# dual-dac-w-32-ch-sh-SH-BOARD.net
KiCad netlist of a schematic drawn in EAGLE
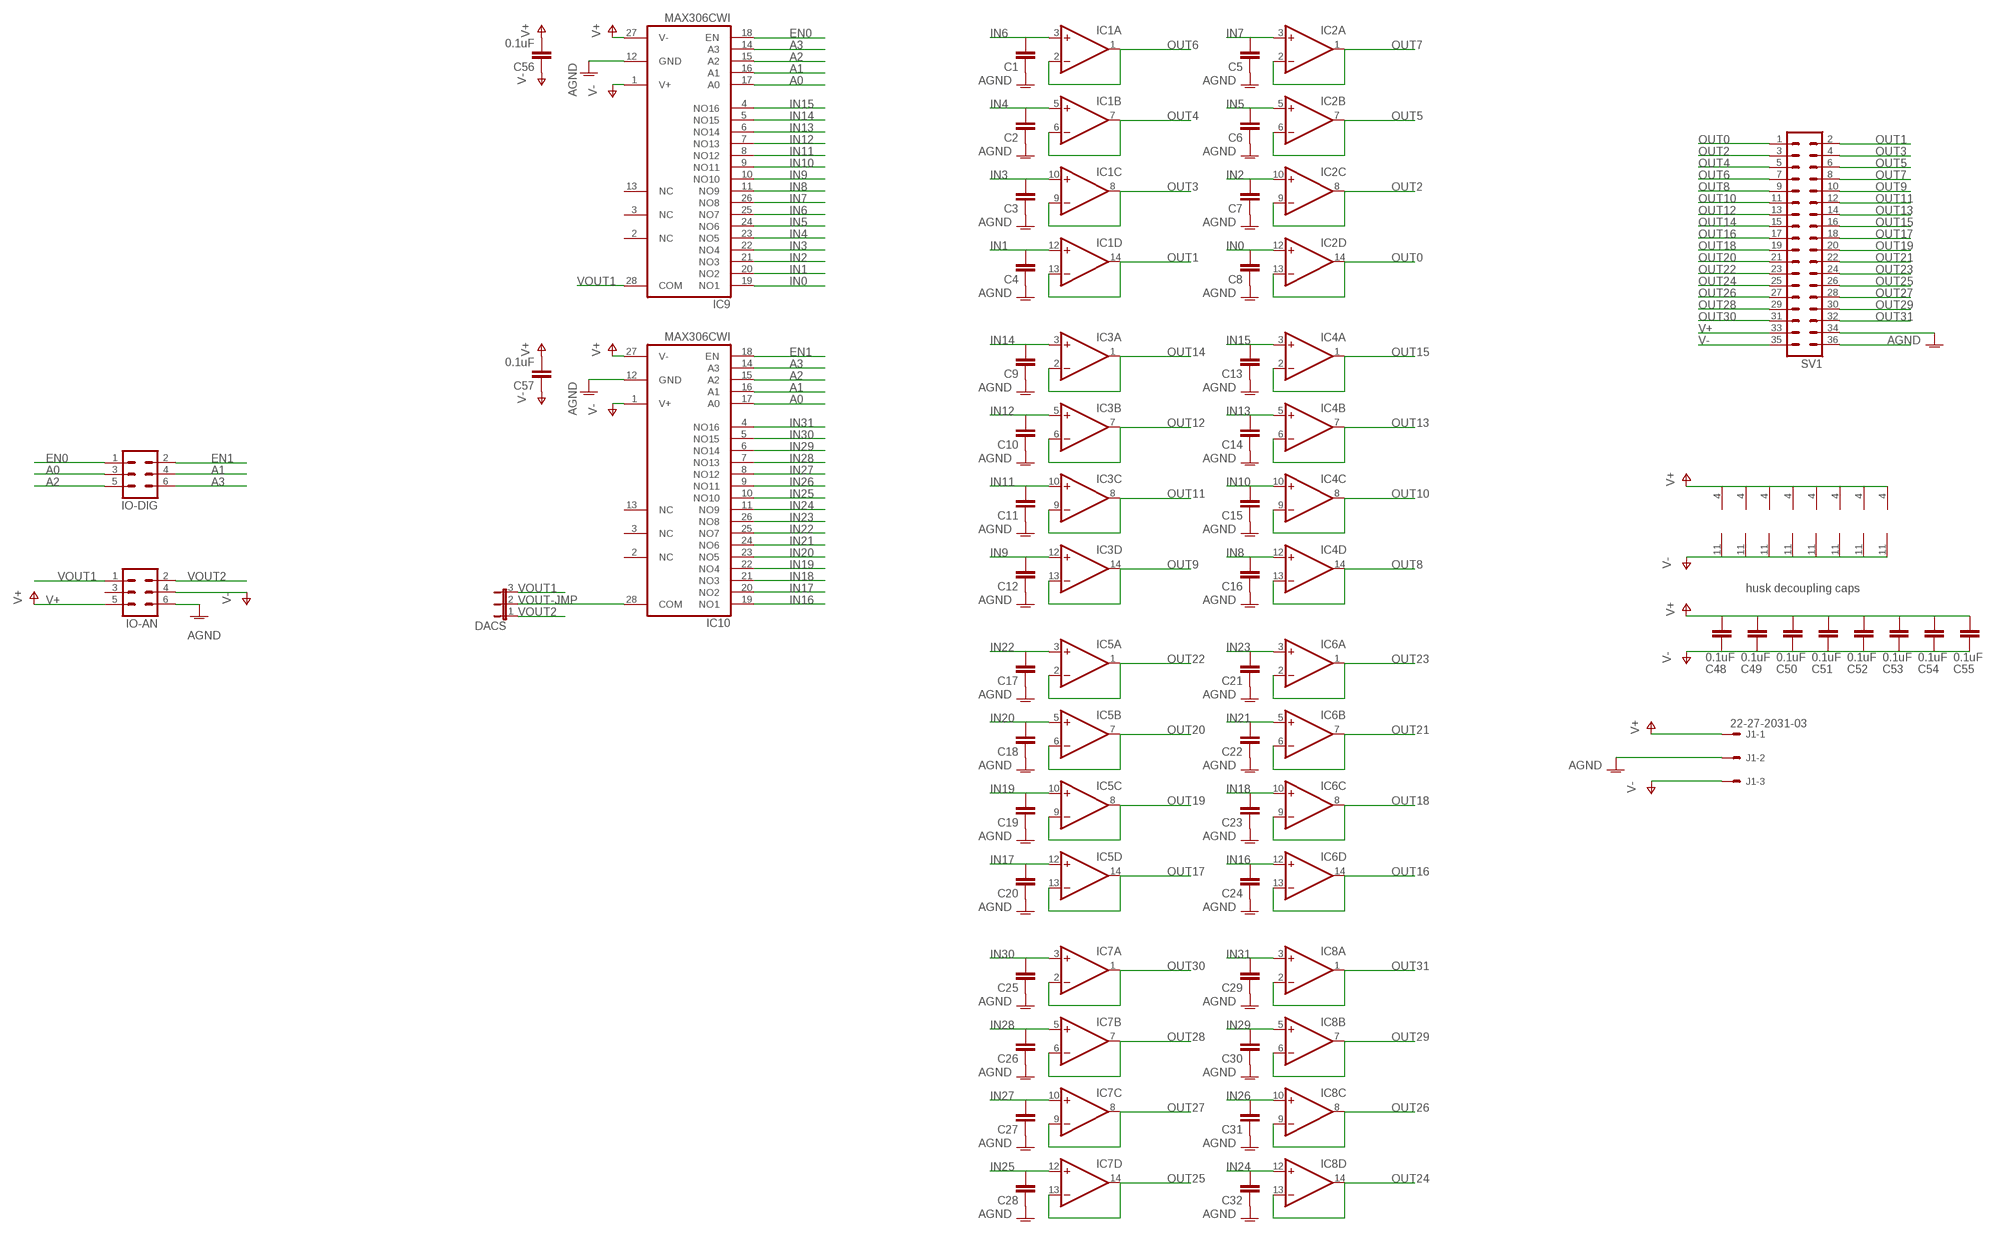
[diagram p0: schematic, sheet 1]

(export (version "E")
  (design (tool "Eeschema 10.0.6"))
  (components
    (comp (ref "C1")
      (value "C-EUC1206")
      (footprint "eagle-import:C1206")
      (libsource (lib "eagle-import") (part "C-EUC1206"))
    )
    (comp (ref "C2")
      (value "C-EUC1206")
      (footprint "eagle-import:C1206")
      (libsource (lib "eagle-import") (part "C-EUC1206"))
    )
    (comp (ref "C3")
      (value "C-EUC1206")
      (footprint "eagle-import:C1206")
      (libsource (lib "eagle-import") (part "C-EUC1206"))
    )
    (comp (ref "C4")
      (value "C-EUC1206")
      (footprint "eagle-import:C1206")
      (libsource (lib "eagle-import") (part "C-EUC1206"))
    )
    (comp (ref "C5")
      (value "C-EUC1206")
      (footprint "eagle-import:C1206")
      (libsource (lib "eagle-import") (part "C-EUC1206"))
    )
    (comp (ref "C6")
      (value "C-EUC1206")
      (footprint "eagle-import:C1206")
      (libsource (lib "eagle-import") (part "C-EUC1206"))
    )
    (comp (ref "C7")
      (value "C-EUC1206")
      (footprint "eagle-import:C1206")
      (libsource (lib "eagle-import") (part "C-EUC1206"))
    )
    (comp (ref "C8")
      (value "C-EUC1206")
      (footprint "eagle-import:C1206")
      (libsource (lib "eagle-import") (part "C-EUC1206"))
    )
    (comp (ref "C9")
      (value "C-EUC1206")
      (footprint "eagle-import:C1206")
      (libsource (lib "eagle-import") (part "C-EUC1206"))
    )
    (comp (ref "C10")
      (value "C-EUC1206")
      (footprint "eagle-import:C1206")
      (libsource (lib "eagle-import") (part "C-EUC1206"))
    )
    (comp (ref "C11")
      (value "C-EUC1206")
      (footprint "eagle-import:C1206")
      (libsource (lib "eagle-import") (part "C-EUC1206"))
    )
    (comp (ref "C12")
      (value "C-EUC1206")
      (footprint "eagle-import:C1206")
      (libsource (lib "eagle-import") (part "C-EUC1206"))
    )
    (comp (ref "C13")
      (value "C-EUC1206")
      (footprint "eagle-import:C1206")
      (libsource (lib "eagle-import") (part "C-EUC1206"))
    )
    (comp (ref "C14")
      (value "C-EUC1206")
      (footprint "eagle-import:C1206")
      (libsource (lib "eagle-import") (part "C-EUC1206"))
    )
    (comp (ref "C15")
      (value "C-EUC1206")
      (footprint "eagle-import:C1206")
      (libsource (lib "eagle-import") (part "C-EUC1206"))
    )
    (comp (ref "C16")
      (value "C-EUC1206")
      (footprint "eagle-import:C1206")
      (libsource (lib "eagle-import") (part "C-EUC1206"))
    )
    (comp (ref "C17")
      (value "C-EUC1206")
      (footprint "eagle-import:C1206")
      (libsource (lib "eagle-import") (part "C-EUC1206"))
    )
    (comp (ref "C18")
      (value "C-EUC1206")
      (footprint "eagle-import:C1206")
      (libsource (lib "eagle-import") (part "C-EUC1206"))
    )
    (comp (ref "C19")
      (value "C-EUC1206")
      (footprint "eagle-import:C1206")
      (libsource (lib "eagle-import") (part "C-EUC1206"))
    )
    (comp (ref "C20")
      (value "C-EUC1206")
      (footprint "eagle-import:C1206")
      (libsource (lib "eagle-import") (part "C-EUC1206"))
    )
    (comp (ref "C21")
      (value "C-EUC1206")
      (footprint "eagle-import:C1206")
      (libsource (lib "eagle-import") (part "C-EUC1206"))
    )
    (comp (ref "C22")
      (value "C-EUC1206")
      (footprint "eagle-import:C1206")
      (libsource (lib "eagle-import") (part "C-EUC1206"))
    )
    (comp (ref "C23")
      (value "C-EUC1206")
      (footprint "eagle-import:C1206")
      (libsource (lib "eagle-import") (part "C-EUC1206"))
    )
    (comp (ref "C24")
      (value "C-EUC1206")
      (footprint "eagle-import:C1206")
      (libsource (lib "eagle-import") (part "C-EUC1206"))
    )
    (comp (ref "C25")
      (value "C-EUC1206")
      (footprint "eagle-import:C1206")
      (libsource (lib "eagle-import") (part "C-EUC1206"))
    )
    (comp (ref "C26")
      (value "C-EUC1206")
      (footprint "eagle-import:C1206")
      (libsource (lib "eagle-import") (part "C-EUC1206"))
    )
    (comp (ref "C27")
      (value "C-EUC1206")
      (footprint "eagle-import:C1206")
      (libsource (lib "eagle-import") (part "C-EUC1206"))
    )
    (comp (ref "C28")
      (value "C-EUC1206")
      (footprint "eagle-import:C1206")
      (libsource (lib "eagle-import") (part "C-EUC1206"))
    )
    (comp (ref "C29")
      (value "C-EUC1206")
      (footprint "eagle-import:C1206")
      (libsource (lib "eagle-import") (part "C-EUC1206"))
    )
    (comp (ref "C30")
      (value "C-EUC1206")
      (footprint "eagle-import:C1206")
      (libsource (lib "eagle-import") (part "C-EUC1206"))
    )
    (comp (ref "C31")
      (value "C-EUC1206")
      (footprint "eagle-import:C1206")
      (libsource (lib "eagle-import") (part "C-EUC1206"))
    )
    (comp (ref "C32")
      (value "C-EUC1206")
      (footprint "eagle-import:C1206")
      (libsource (lib "eagle-import") (part "C-EUC1206"))
    )
    (comp (ref "C48")
      (value "0.1uF")
      (footprint "eagle-import:C0603")
      (libsource (lib "eagle-import") (part "C-EUC0603"))
    )
    (comp (ref "C49")
      (value "0.1uF")
      (footprint "eagle-import:C0603")
      (libsource (lib "eagle-import") (part "C-EUC0603"))
    )
    (comp (ref "C50")
      (value "0.1uF")
      (footprint "eagle-import:C0603")
      (libsource (lib "eagle-import") (part "C-EUC0603"))
    )
    (comp (ref "C51")
      (value "0.1uF")
      (footprint "eagle-import:C0603")
      (libsource (lib "eagle-import") (part "C-EUC0603"))
    )
    (comp (ref "C52")
      (value "0.1uF")
      (footprint "eagle-import:C0603")
      (libsource (lib "eagle-import") (part "C-EUC0603"))
    )
    (comp (ref "C53")
      (value "0.1uF")
      (footprint "eagle-import:C0603")
      (libsource (lib "eagle-import") (part "C-EUC0603"))
    )
    (comp (ref "C54")
      (value "0.1uF")
      (footprint "eagle-import:C0603")
      (libsource (lib "eagle-import") (part "C-EUC0603"))
    )
    (comp (ref "C55")
      (value "0.1uF")
      (footprint "eagle-import:C0603")
      (libsource (lib "eagle-import") (part "C-EUC0603"))
    )
    (comp (ref "C56")
      (value "0.1uF")
      (footprint "eagle-import:C0603")
      (libsource (lib "eagle-import") (part "C-EUC0603"))
    )
    (comp (ref "C57")
      (value "0.1uF")
      (footprint "eagle-import:C0603")
      (libsource (lib "eagle-import") (part "C-EUC0603"))
    )
    (comp (ref "DACS")
      (value "JP2E")
      (footprint "eagle-import:JP2")
      (libsource (lib "eagle-import") (part "JP2E"))
    )
    (comp (ref "IC1")
      (value "TL074D")
      (footprint "eagle-import:SO14")
      (libsource (lib "eagle-import") (part "TL074D"))
    )
    (comp (ref "IC2")
      (value "TL074D")
      (footprint "eagle-import:SO14")
      (libsource (lib "eagle-import") (part "TL074D"))
    )
    (comp (ref "IC3")
      (value "TL074D")
      (footprint "eagle-import:SO14")
      (libsource (lib "eagle-import") (part "TL074D"))
    )
    (comp (ref "IC4")
      (value "TL074D")
      (footprint "eagle-import:SO14")
      (libsource (lib "eagle-import") (part "TL074D"))
    )
    (comp (ref "IC5")
      (value "TL074D")
      (footprint "eagle-import:SO14")
      (libsource (lib "eagle-import") (part "TL074D"))
    )
    (comp (ref "IC6")
      (value "TL074D")
      (footprint "eagle-import:SO14")
      (libsource (lib "eagle-import") (part "TL074D"))
    )
    (comp (ref "IC7")
      (value "TL074D")
      (footprint "eagle-import:SO14")
      (libsource (lib "eagle-import") (part "TL074D"))
    )
    (comp (ref "IC8")
      (value "TL074D")
      (footprint "eagle-import:SO14")
      (libsource (lib "eagle-import") (part "TL074D"))
    )
    (comp (ref "IC9")
      (value "MAX306CWI")
      (footprint "eagle-import:SO28L")
      (fields (field (name "MF") "MAXIM"))
      (libsource (lib "eagle-import") (part "MAX306CWI"))
    )
    (comp (ref "IC10")
      (value "MAX306CWI")
      (footprint "eagle-import:SO28L")
      (fields (field (name "MF") "MAXIM"))
      (libsource (lib "eagle-import") (part "MAX306CWI"))
    )
    (comp (ref "IO-AN")
      (value "MA03-2")
      (footprint "eagle-import:MA03-2")
      (libsource (lib "eagle-import") (part "MA03-2"))
    )
    (comp (ref "IO-DIG")
      (value "MA03-2")
      (footprint "eagle-import:MA03-2")
      (libsource (lib "eagle-import") (part "MA03-2"))
    )
    (comp (ref "J1")
      (value "22-27-2031-03")
      (footprint "eagle-import:6410-03")
      (libsource (lib "eagle-import") (part "22-?-0327-2031"))
    )
    (comp (ref "SV1")
      (value "MA18-2")
      (footprint "eagle-import:MA18-2")
      (libsource (lib "eagle-import") (part "MA18-2"))
    )
  )
  (nets
    (net (code "1") (name "/A0") (class "Default")
      (node (ref "IC10") (pin "17") (pinfunction "A0_17") (pintype "input"))
      (node (ref "IC9") (pin "17") (pinfunction "A0_17") (pintype "input"))
      (node (ref "IO-DIG") (pin "3") (pinfunction "3_3") (pintype "passive"))
    )
    (net (code "2") (name "/A1") (class "Default")
      (node (ref "IC10") (pin "16") (pinfunction "A1_16") (pintype "input"))
      (node (ref "IC9") (pin "16") (pinfunction "A1_16") (pintype "input"))
      (node (ref "IO-DIG") (pin "4") (pinfunction "4_4") (pintype "passive"))
    )
    (net (code "3") (name "/A2") (class "Default")
      (node (ref "IC10") (pin "15") (pinfunction "A2_15") (pintype "input"))
      (node (ref "IC9") (pin "15") (pinfunction "A2_15") (pintype "input"))
      (node (ref "IO-DIG") (pin "5") (pinfunction "5_5") (pintype "passive"))
    )
    (net (code "4") (name "/A3") (class "Default")
      (node (ref "IC10") (pin "14") (pinfunction "A3_14") (pintype "input"))
      (node (ref "IC9") (pin "14") (pinfunction "A3_14") (pintype "input"))
      (node (ref "IO-DIG") (pin "6") (pinfunction "6_6") (pintype "passive"))
    )
    (net (code "5") (name "/EN0") (class "Default")
      (node (ref "IC9") (pin "18") (pinfunction "EN_18") (pintype "input"))
      (node (ref "IO-DIG") (pin "1") (pinfunction "1_1") (pintype "passive"))
    )
    (net (code "6") (name "/EN1") (class "Default")
      (node (ref "IC10") (pin "18") (pinfunction "EN_18") (pintype "input"))
      (node (ref "IO-DIG") (pin "2") (pinfunction "2_2") (pintype "passive"))
    )
    (net (code "7") (name "/IN0") (class "Default")
      (node (ref "C8") (pin "2") (pinfunction "2_2") (pintype "passive"))
      (node (ref "IC2") (pin "12") (pinfunction "+IN_12") (pintype "input"))
      (node (ref "IC9") (pin "19") (pinfunction "NO1_19") (pintype "passive"))
    )
    (net (code "8") (name "/IN1") (class "Default")
      (node (ref "C4") (pin "2") (pinfunction "2_2") (pintype "passive"))
      (node (ref "IC1") (pin "12") (pinfunction "+IN_12") (pintype "input"))
      (node (ref "IC9") (pin "20") (pinfunction "NO2_20") (pintype "passive"))
    )
    (net (code "9") (name "/IN2") (class "Default")
      (node (ref "C7") (pin "2") (pinfunction "2_2") (pintype "passive"))
      (node (ref "IC2") (pin "10") (pinfunction "+IN_10") (pintype "input"))
      (node (ref "IC9") (pin "21") (pinfunction "NO3_21") (pintype "passive"))
    )
    (net (code "10") (name "/IN3") (class "Default")
      (node (ref "C3") (pin "2") (pinfunction "2_2") (pintype "passive"))
      (node (ref "IC1") (pin "10") (pinfunction "+IN_10") (pintype "input"))
      (node (ref "IC9") (pin "22") (pinfunction "NO4_22") (pintype "passive"))
    )
    (net (code "11") (name "/IN4") (class "Default")
      (node (ref "C2") (pin "2") (pinfunction "2_2") (pintype "passive"))
      (node (ref "IC1") (pin "5") (pinfunction "+IN_5") (pintype "input"))
      (node (ref "IC9") (pin "23") (pinfunction "NO5_23") (pintype "passive"))
    )
    (net (code "12") (name "/IN5") (class "Default")
      (node (ref "C6") (pin "2") (pinfunction "2_2") (pintype "passive"))
      (node (ref "IC2") (pin "5") (pinfunction "+IN_5") (pintype "input"))
      (node (ref "IC9") (pin "24") (pinfunction "NO6_24") (pintype "passive"))
    )
    (net (code "13") (name "/IN6") (class "Default")
      (node (ref "C1") (pin "2") (pinfunction "2_2") (pintype "passive"))
      (node (ref "IC1") (pin "3") (pinfunction "+IN_3") (pintype "input"))
      (node (ref "IC9") (pin "25") (pinfunction "NO7_25") (pintype "passive"))
    )
    (net (code "14") (name "/IN7") (class "Default")
      (node (ref "C5") (pin "2") (pinfunction "2_2") (pintype "passive"))
      (node (ref "IC2") (pin "3") (pinfunction "+IN_3") (pintype "input"))
      (node (ref "IC9") (pin "26") (pinfunction "NO8_26") (pintype "passive"))
    )
    (net (code "15") (name "/IN8") (class "Default")
      (node (ref "C16") (pin "2") (pinfunction "2_2") (pintype "passive"))
      (node (ref "IC4") (pin "12") (pinfunction "+IN_12") (pintype "input"))
      (node (ref "IC9") (pin "11") (pinfunction "NO9_11") (pintype "passive"))
    )
    (net (code "16") (name "/IN9") (class "Default")
      (node (ref "C12") (pin "2") (pinfunction "2_2") (pintype "passive"))
      (node (ref "IC3") (pin "12") (pinfunction "+IN_12") (pintype "input"))
      (node (ref "IC9") (pin "10") (pinfunction "NO10_10") (pintype "passive"))
    )
    (net (code "17") (name "/IN10") (class "Default")
      (node (ref "C15") (pin "2") (pinfunction "2_2") (pintype "passive"))
      (node (ref "IC4") (pin "10") (pinfunction "+IN_10") (pintype "input"))
      (node (ref "IC9") (pin "9") (pinfunction "NO11_9") (pintype "passive"))
    )
    (net (code "18") (name "/IN11") (class "Default")
      (node (ref "C11") (pin "2") (pinfunction "2_2") (pintype "passive"))
      (node (ref "IC3") (pin "10") (pinfunction "+IN_10") (pintype "input"))
      (node (ref "IC9") (pin "8") (pinfunction "NO12_8") (pintype "passive"))
    )
    (net (code "19") (name "/IN12") (class "Default")
      (node (ref "C10") (pin "2") (pinfunction "2_2") (pintype "passive"))
      (node (ref "IC3") (pin "5") (pinfunction "+IN_5") (pintype "input"))
      (node (ref "IC9") (pin "7") (pinfunction "NO13_7") (pintype "passive"))
    )
    (net (code "20") (name "/IN13") (class "Default")
      (node (ref "C14") (pin "2") (pinfunction "2_2") (pintype "passive"))
      (node (ref "IC4") (pin "5") (pinfunction "+IN_5") (pintype "input"))
      (node (ref "IC9") (pin "6") (pinfunction "NO14_6") (pintype "passive"))
    )
    (net (code "21") (name "/IN14") (class "Default")
      (node (ref "C9") (pin "2") (pinfunction "2_2") (pintype "passive"))
      (node (ref "IC3") (pin "3") (pinfunction "+IN_3") (pintype "input"))
      (node (ref "IC9") (pin "5") (pinfunction "NO15_5") (pintype "passive"))
    )
    (net (code "22") (name "/IN15") (class "Default")
      (node (ref "C13") (pin "2") (pinfunction "2_2") (pintype "passive"))
      (node (ref "IC4") (pin "3") (pinfunction "+IN_3") (pintype "input"))
      (node (ref "IC9") (pin "4") (pinfunction "NO16_4") (pintype "passive"))
    )
    (net (code "23") (name "/IN16") (class "Default")
      (node (ref "C24") (pin "2") (pinfunction "2_2") (pintype "passive"))
      (node (ref "IC10") (pin "19") (pinfunction "NO1_19") (pintype "passive"))
      (node (ref "IC6") (pin "12") (pinfunction "+IN_12") (pintype "input"))
    )
    (net (code "24") (name "/IN17") (class "Default")
      (node (ref "C20") (pin "2") (pinfunction "2_2") (pintype "passive"))
      (node (ref "IC10") (pin "20") (pinfunction "NO2_20") (pintype "passive"))
      (node (ref "IC5") (pin "12") (pinfunction "+IN_12") (pintype "input"))
    )
    (net (code "25") (name "/IN18") (class "Default")
      (node (ref "C23") (pin "2") (pinfunction "2_2") (pintype "passive"))
      (node (ref "IC10") (pin "21") (pinfunction "NO3_21") (pintype "passive"))
      (node (ref "IC6") (pin "10") (pinfunction "+IN_10") (pintype "input"))
    )
    (net (code "26") (name "/IN19") (class "Default")
      (node (ref "C19") (pin "2") (pinfunction "2_2") (pintype "passive"))
      (node (ref "IC10") (pin "22") (pinfunction "NO4_22") (pintype "passive"))
      (node (ref "IC5") (pin "10") (pinfunction "+IN_10") (pintype "input"))
    )
    (net (code "27") (name "/IN20") (class "Default")
      (node (ref "C18") (pin "2") (pinfunction "2_2") (pintype "passive"))
      (node (ref "IC10") (pin "23") (pinfunction "NO5_23") (pintype "passive"))
      (node (ref "IC5") (pin "5") (pinfunction "+IN_5") (pintype "input"))
    )
    (net (code "28") (name "/IN21") (class "Default")
      (node (ref "C22") (pin "2") (pinfunction "2_2") (pintype "passive"))
      (node (ref "IC10") (pin "24") (pinfunction "NO6_24") (pintype "passive"))
      (node (ref "IC6") (pin "5") (pinfunction "+IN_5") (pintype "input"))
    )
    (net (code "29") (name "/IN22") (class "Default")
      (node (ref "C17") (pin "2") (pinfunction "2_2") (pintype "passive"))
      (node (ref "IC10") (pin "25") (pinfunction "NO7_25") (pintype "passive"))
      (node (ref "IC5") (pin "3") (pinfunction "+IN_3") (pintype "input"))
    )
    (net (code "30") (name "/IN23") (class "Default")
      (node (ref "C21") (pin "2") (pinfunction "2_2") (pintype "passive"))
      (node (ref "IC10") (pin "26") (pinfunction "NO8_26") (pintype "passive"))
      (node (ref "IC6") (pin "3") (pinfunction "+IN_3") (pintype "input"))
    )
    (net (code "31") (name "/IN24") (class "Default")
      (node (ref "C32") (pin "2") (pinfunction "2_2") (pintype "passive"))
      (node (ref "IC10") (pin "11") (pinfunction "NO9_11") (pintype "passive"))
      (node (ref "IC8") (pin "12") (pinfunction "+IN_12") (pintype "input"))
    )
    (net (code "32") (name "/IN25") (class "Default")
      (node (ref "C28") (pin "2") (pinfunction "2_2") (pintype "passive"))
      (node (ref "IC10") (pin "10") (pinfunction "NO10_10") (pintype "passive"))
      (node (ref "IC7") (pin "12") (pinfunction "+IN_12") (pintype "input"))
    )
    (net (code "33") (name "/IN26") (class "Default")
      (node (ref "C31") (pin "2") (pinfunction "2_2") (pintype "passive"))
      (node (ref "IC10") (pin "9") (pinfunction "NO11_9") (pintype "passive"))
      (node (ref "IC8") (pin "10") (pinfunction "+IN_10") (pintype "input"))
    )
    (net (code "34") (name "/IN27") (class "Default")
      (node (ref "C27") (pin "2") (pinfunction "2_2") (pintype "passive"))
      (node (ref "IC10") (pin "8") (pinfunction "NO12_8") (pintype "passive"))
      (node (ref "IC7") (pin "10") (pinfunction "+IN_10") (pintype "input"))
    )
    (net (code "35") (name "/IN28") (class "Default")
      (node (ref "C26") (pin "2") (pinfunction "2_2") (pintype "passive"))
      (node (ref "IC10") (pin "7") (pinfunction "NO13_7") (pintype "passive"))
      (node (ref "IC7") (pin "5") (pinfunction "+IN_5") (pintype "input"))
    )
    (net (code "36") (name "/IN29") (class "Default")
      (node (ref "C30") (pin "2") (pinfunction "2_2") (pintype "passive"))
      (node (ref "IC10") (pin "6") (pinfunction "NO14_6") (pintype "passive"))
      (node (ref "IC8") (pin "5") (pinfunction "+IN_5") (pintype "input"))
    )
    (net (code "37") (name "/IN30") (class "Default")
      (node (ref "C25") (pin "2") (pinfunction "2_2") (pintype "passive"))
      (node (ref "IC10") (pin "5") (pinfunction "NO15_5") (pintype "passive"))
      (node (ref "IC7") (pin "3") (pinfunction "+IN_3") (pintype "input"))
    )
    (net (code "38") (name "/IN31") (class "Default")
      (node (ref "C29") (pin "2") (pinfunction "2_2") (pintype "passive"))
      (node (ref "IC10") (pin "4") (pinfunction "NO16_4") (pintype "passive"))
      (node (ref "IC8") (pin "3") (pinfunction "+IN_3") (pintype "input"))
    )
    (net (code "39") (name "/OUT0") (class "Default")
      (node (ref "IC2") (pin "13") (pinfunction "-IN_13") (pintype "input"))
      (node (ref "IC2") (pin "14") (pinfunction "OUT_14") (pintype "output"))
      (node (ref "SV1") (pin "1") (pinfunction "1_1") (pintype "passive"))
    )
    (net (code "40") (name "/OUT1") (class "Default")
      (node (ref "IC1") (pin "13") (pinfunction "-IN_13") (pintype "input"))
      (node (ref "IC1") (pin "14") (pinfunction "OUT_14") (pintype "output"))
      (node (ref "SV1") (pin "2") (pinfunction "2_2") (pintype "passive"))
    )
    (net (code "41") (name "/OUT2") (class "Default")
      (node (ref "IC2") (pin "8") (pinfunction "OUT_8") (pintype "output"))
      (node (ref "IC2") (pin "9") (pinfunction "-IN_9") (pintype "input"))
      (node (ref "SV1") (pin "3") (pinfunction "3_3") (pintype "passive"))
    )
    (net (code "42") (name "/OUT3") (class "Default")
      (node (ref "IC1") (pin "8") (pinfunction "OUT_8") (pintype "output"))
      (node (ref "IC1") (pin "9") (pinfunction "-IN_9") (pintype "input"))
      (node (ref "SV1") (pin "4") (pinfunction "4_4") (pintype "passive"))
    )
    (net (code "43") (name "/OUT4") (class "Default")
      (node (ref "IC1") (pin "6") (pinfunction "-IN_6") (pintype "input"))
      (node (ref "IC1") (pin "7") (pinfunction "OUT_7") (pintype "output"))
      (node (ref "SV1") (pin "5") (pinfunction "5_5") (pintype "passive"))
    )
    (net (code "44") (name "/OUT5") (class "Default")
      (node (ref "IC2") (pin "6") (pinfunction "-IN_6") (pintype "input"))
      (node (ref "IC2") (pin "7") (pinfunction "OUT_7") (pintype "output"))
      (node (ref "SV1") (pin "6") (pinfunction "6_6") (pintype "passive"))
    )
    (net (code "45") (name "/OUT6") (class "Default")
      (node (ref "IC1") (pin "1") (pinfunction "OUT_1") (pintype "output"))
      (node (ref "IC1") (pin "2") (pinfunction "-IN_2") (pintype "input"))
      (node (ref "SV1") (pin "7") (pinfunction "7_7") (pintype "passive"))
    )
    (net (code "46") (name "/OUT7") (class "Default")
      (node (ref "IC2") (pin "1") (pinfunction "OUT_1") (pintype "output"))
      (node (ref "IC2") (pin "2") (pinfunction "-IN_2") (pintype "input"))
      (node (ref "SV1") (pin "8") (pinfunction "8_8") (pintype "passive"))
    )
    (net (code "47") (name "/OUT8") (class "Default")
      (node (ref "IC4") (pin "13") (pinfunction "-IN_13") (pintype "input"))
      (node (ref "IC4") (pin "14") (pinfunction "OUT_14") (pintype "output"))
      (node (ref "SV1") (pin "9") (pinfunction "9_9") (pintype "passive"))
    )
    (net (code "48") (name "/OUT9") (class "Default")
      (node (ref "IC3") (pin "13") (pinfunction "-IN_13") (pintype "input"))
      (node (ref "IC3") (pin "14") (pinfunction "OUT_14") (pintype "output"))
      (node (ref "SV1") (pin "10") (pinfunction "10_10") (pintype "passive"))
    )
    (net (code "49") (name "/OUT10") (class "Default")
      (node (ref "IC4") (pin "8") (pinfunction "OUT_8") (pintype "output"))
      (node (ref "IC4") (pin "9") (pinfunction "-IN_9") (pintype "input"))
      (node (ref "SV1") (pin "11") (pinfunction "11_11") (pintype "passive"))
    )
    (net (code "50") (name "/OUT11") (class "Default")
      (node (ref "IC3") (pin "8") (pinfunction "OUT_8") (pintype "output"))
      (node (ref "IC3") (pin "9") (pinfunction "-IN_9") (pintype "input"))
      (node (ref "SV1") (pin "12") (pinfunction "12_12") (pintype "passive"))
    )
    (net (code "51") (name "/OUT12") (class "Default")
      (node (ref "IC3") (pin "6") (pinfunction "-IN_6") (pintype "input"))
      (node (ref "IC3") (pin "7") (pinfunction "OUT_7") (pintype "output"))
      (node (ref "SV1") (pin "13") (pinfunction "13_13") (pintype "passive"))
    )
    (net (code "52") (name "/OUT13") (class "Default")
      (node (ref "IC4") (pin "6") (pinfunction "-IN_6") (pintype "input"))
      (node (ref "IC4") (pin "7") (pinfunction "OUT_7") (pintype "output"))
      (node (ref "SV1") (pin "14") (pinfunction "14_14") (pintype "passive"))
    )
    (net (code "53") (name "/OUT14") (class "Default")
      (node (ref "IC3") (pin "1") (pinfunction "OUT_1") (pintype "output"))
      (node (ref "IC3") (pin "2") (pinfunction "-IN_2") (pintype "input"))
      (node (ref "SV1") (pin "15") (pinfunction "15_15") (pintype "passive"))
    )
    (net (code "54") (name "/OUT15") (class "Default")
      (node (ref "IC4") (pin "1") (pinfunction "OUT_1") (pintype "output"))
      (node (ref "IC4") (pin "2") (pinfunction "-IN_2") (pintype "input"))
      (node (ref "SV1") (pin "16") (pinfunction "16_16") (pintype "passive"))
    )
    (net (code "55") (name "/OUT16") (class "Default")
      (node (ref "IC6") (pin "13") (pinfunction "-IN_13") (pintype "input"))
      (node (ref "IC6") (pin "14") (pinfunction "OUT_14") (pintype "output"))
      (node (ref "SV1") (pin "17") (pinfunction "17_17") (pintype "passive"))
    )
    (net (code "56") (name "/OUT17") (class "Default")
      (node (ref "IC5") (pin "13") (pinfunction "-IN_13") (pintype "input"))
      (node (ref "IC5") (pin "14") (pinfunction "OUT_14") (pintype "output"))
      (node (ref "SV1") (pin "18") (pinfunction "18_18") (pintype "passive"))
    )
    (net (code "57") (name "/OUT18") (class "Default")
      (node (ref "IC6") (pin "8") (pinfunction "OUT_8") (pintype "output"))
      (node (ref "IC6") (pin "9") (pinfunction "-IN_9") (pintype "input"))
      (node (ref "SV1") (pin "19") (pinfunction "19_19") (pintype "passive"))
    )
    (net (code "58") (name "/OUT19") (class "Default")
      (node (ref "IC5") (pin "8") (pinfunction "OUT_8") (pintype "output"))
      (node (ref "IC5") (pin "9") (pinfunction "-IN_9") (pintype "input"))
      (node (ref "SV1") (pin "20") (pinfunction "20_20") (pintype "passive"))
    )
    (net (code "59") (name "/OUT20") (class "Default")
      (node (ref "IC5") (pin "6") (pinfunction "-IN_6") (pintype "input"))
      (node (ref "IC5") (pin "7") (pinfunction "OUT_7") (pintype "output"))
      (node (ref "SV1") (pin "21") (pinfunction "21_21") (pintype "passive"))
    )
    (net (code "60") (name "/OUT21") (class "Default")
      (node (ref "IC6") (pin "6") (pinfunction "-IN_6") (pintype "input"))
      (node (ref "IC6") (pin "7") (pinfunction "OUT_7") (pintype "output"))
      (node (ref "SV1") (pin "22") (pinfunction "22_22") (pintype "passive"))
    )
    (net (code "61") (name "/OUT22") (class "Default")
      (node (ref "IC5") (pin "1") (pinfunction "OUT_1") (pintype "output"))
      (node (ref "IC5") (pin "2") (pinfunction "-IN_2") (pintype "input"))
      (node (ref "SV1") (pin "23") (pinfunction "23_23") (pintype "passive"))
    )
    (net (code "62") (name "/OUT23") (class "Default")
      (node (ref "IC6") (pin "1") (pinfunction "OUT_1") (pintype "output"))
      (node (ref "IC6") (pin "2") (pinfunction "-IN_2") (pintype "input"))
      (node (ref "SV1") (pin "24") (pinfunction "24_24") (pintype "passive"))
    )
    (net (code "63") (name "/OUT24") (class "Default")
      (node (ref "IC8") (pin "13") (pinfunction "-IN_13") (pintype "input"))
      (node (ref "IC8") (pin "14") (pinfunction "OUT_14") (pintype "output"))
      (node (ref "SV1") (pin "25") (pinfunction "25_25") (pintype "passive"))
    )
    (net (code "64") (name "/OUT25") (class "Default")
      (node (ref "IC7") (pin "13") (pinfunction "-IN_13") (pintype "input"))
      (node (ref "IC7") (pin "14") (pinfunction "OUT_14") (pintype "output"))
      (node (ref "SV1") (pin "26") (pinfunction "26_26") (pintype "passive"))
    )
    (net (code "65") (name "/OUT26") (class "Default")
      (node (ref "IC8") (pin "8") (pinfunction "OUT_8") (pintype "output"))
      (node (ref "IC8") (pin "9") (pinfunction "-IN_9") (pintype "input"))
      (node (ref "SV1") (pin "27") (pinfunction "27_27") (pintype "passive"))
    )
    (net (code "66") (name "/OUT27") (class "Default")
      (node (ref "IC7") (pin "8") (pinfunction "OUT_8") (pintype "output"))
      (node (ref "IC7") (pin "9") (pinfunction "-IN_9") (pintype "input"))
      (node (ref "SV1") (pin "28") (pinfunction "28_28") (pintype "passive"))
    )
    (net (code "67") (name "/OUT28") (class "Default")
      (node (ref "IC7") (pin "6") (pinfunction "-IN_6") (pintype "input"))
      (node (ref "IC7") (pin "7") (pinfunction "OUT_7") (pintype "output"))
      (node (ref "SV1") (pin "29") (pinfunction "29_29") (pintype "passive"))
    )
    (net (code "68") (name "/OUT29") (class "Default")
      (node (ref "IC8") (pin "6") (pinfunction "-IN_6") (pintype "input"))
      (node (ref "IC8") (pin "7") (pinfunction "OUT_7") (pintype "output"))
      (node (ref "SV1") (pin "30") (pinfunction "30_30") (pintype "passive"))
    )
    (net (code "69") (name "/OUT30") (class "Default")
      (node (ref "IC7") (pin "1") (pinfunction "OUT_1") (pintype "output"))
      (node (ref "IC7") (pin "2") (pinfunction "-IN_2") (pintype "input"))
      (node (ref "SV1") (pin "31") (pinfunction "31_31") (pintype "passive"))
    )
    (net (code "70") (name "/OUT31") (class "Default")
      (node (ref "IC8") (pin "1") (pinfunction "OUT_1") (pintype "output"))
      (node (ref "IC8") (pin "2") (pinfunction "-IN_2") (pintype "input"))
      (node (ref "SV1") (pin "32") (pinfunction "32_32") (pintype "passive"))
    )
    (net (code "71") (name "/VOUT-JMP") (class "Default")
      (node (ref "DACS") (pin "2") (pinfunction "2_2") (pintype "passive"))
      (node (ref "IC10") (pin "28") (pinfunction "COM_28") (pintype "passive"))
    )
    (net (code "72") (name "/VOUT1") (class "Default")
      (node (ref "DACS") (pin "3") (pinfunction "3_3") (pintype "passive"))
      (node (ref "IC9") (pin "28") (pinfunction "COM_28") (pintype "passive"))
      (node (ref "IO-AN") (pin "1") (pinfunction "1_1") (pintype "passive"))
    )
    (net (code "73") (name "/VOUT2") (class "Default")
      (node (ref "DACS") (pin "1") (pinfunction "1_1") (pintype "passive"))
      (node (ref "IO-AN") (pin "2") (pinfunction "2_2") (pintype "passive"))
    )
    (net (code "74") (name "AGND") (class "Default")
      (node (ref "C1") (pin "1") (pinfunction "1_1") (pintype "passive"))
      (node (ref "C10") (pin "1") (pinfunction "1_1") (pintype "passive"))
      (node (ref "C11") (pin "1") (pinfunction "1_1") (pintype "passive"))
      (node (ref "C12") (pin "1") (pinfunction "1_1") (pintype "passive"))
      (node (ref "C13") (pin "1") (pinfunction "1_1") (pintype "passive"))
      (node (ref "C14") (pin "1") (pinfunction "1_1") (pintype "passive"))
      (node (ref "C15") (pin "1") (pinfunction "1_1") (pintype "passive"))
      (node (ref "C16") (pin "1") (pinfunction "1_1") (pintype "passive"))
      (node (ref "C17") (pin "1") (pinfunction "1_1") (pintype "passive"))
      (node (ref "C18") (pin "1") (pinfunction "1_1") (pintype "passive"))
      (node (ref "C19") (pin "1") (pinfunction "1_1") (pintype "passive"))
      (node (ref "C2") (pin "1") (pinfunction "1_1") (pintype "passive"))
      (node (ref "C20") (pin "1") (pinfunction "1_1") (pintype "passive"))
      (node (ref "C21") (pin "1") (pinfunction "1_1") (pintype "passive"))
      (node (ref "C22") (pin "1") (pinfunction "1_1") (pintype "passive"))
      (node (ref "C23") (pin "1") (pinfunction "1_1") (pintype "passive"))
      (node (ref "C24") (pin "1") (pinfunction "1_1") (pintype "passive"))
      (node (ref "C25") (pin "1") (pinfunction "1_1") (pintype "passive"))
      (node (ref "C26") (pin "1") (pinfunction "1_1") (pintype "passive"))
      (node (ref "C27") (pin "1") (pinfunction "1_1") (pintype "passive"))
      (node (ref "C28") (pin "1") (pinfunction "1_1") (pintype "passive"))
      (node (ref "C29") (pin "1") (pinfunction "1_1") (pintype "passive"))
      (node (ref "C3") (pin "1") (pinfunction "1_1") (pintype "passive"))
      (node (ref "C30") (pin "1") (pinfunction "1_1") (pintype "passive"))
      (node (ref "C31") (pin "1") (pinfunction "1_1") (pintype "passive"))
      (node (ref "C32") (pin "1") (pinfunction "1_1") (pintype "passive"))
      (node (ref "C4") (pin "1") (pinfunction "1_1") (pintype "passive"))
      (node (ref "C5") (pin "1") (pinfunction "1_1") (pintype "passive"))
      (node (ref "C6") (pin "1") (pinfunction "1_1") (pintype "passive"))
      (node (ref "C7") (pin "1") (pinfunction "1_1") (pintype "passive"))
      (node (ref "C8") (pin "1") (pinfunction "1_1") (pintype "passive"))
      (node (ref "C9") (pin "1") (pinfunction "1_1") (pintype "passive"))
      (node (ref "IC10") (pin "12") (pinfunction "GND_12") (pintype "power_in"))
      (node (ref "IC9") (pin "12") (pinfunction "GND_12") (pintype "power_in"))
      (node (ref "IO-AN") (pin "6") (pinfunction "6_6") (pintype "passive"))
      (node (ref "J1") (pin "2") (pinfunction "S_2") (pintype "passive"))
      (node (ref "SV1") (pin "34") (pinfunction "34_34") (pintype "passive"))
    )
    (net (code "75") (name "V+") (class "Default")
      (node (ref "C48") (pin "2") (pinfunction "2_2") (pintype "passive"))
      (node (ref "C49") (pin "2") (pinfunction "2_2") (pintype "passive"))
      (node (ref "C50") (pin "2") (pinfunction "2_2") (pintype "passive"))
      (node (ref "C51") (pin "2") (pinfunction "2_2") (pintype "passive"))
      (node (ref "C52") (pin "2") (pinfunction "2_2") (pintype "passive"))
      (node (ref "C53") (pin "2") (pinfunction "2_2") (pintype "passive"))
      (node (ref "C54") (pin "2") (pinfunction "2_2") (pintype "passive"))
      (node (ref "C55") (pin "2") (pinfunction "2_2") (pintype "passive"))
      (node (ref "C56") (pin "2") (pinfunction "2_2") (pintype "passive"))
      (node (ref "C57") (pin "2") (pinfunction "2_2") (pintype "passive"))
      (node (ref "IC1") (pin "4") (pinfunction "V+_4") (pintype "power_in"))
      (node (ref "IC10") (pin "27") (pinfunction "V-_27") (pintype "power_in"))
      (node (ref "IC2") (pin "4") (pinfunction "V+_4") (pintype "power_in"))
      (node (ref "IC3") (pin "4") (pinfunction "V+_4") (pintype "power_in"))
      (node (ref "IC4") (pin "4") (pinfunction "V+_4") (pintype "power_in"))
      (node (ref "IC5") (pin "4") (pinfunction "V+_4") (pintype "power_in"))
      (node (ref "IC6") (pin "4") (pinfunction "V+_4") (pintype "power_in"))
      (node (ref "IC7") (pin "4") (pinfunction "V+_4") (pintype "power_in"))
      (node (ref "IC8") (pin "4") (pinfunction "V+_4") (pintype "power_in"))
      (node (ref "IC9") (pin "27") (pinfunction "V-_27") (pintype "power_in"))
      (node (ref "IO-AN") (pin "5") (pinfunction "5_5") (pintype "passive"))
      (node (ref "J1") (pin "1") (pinfunction "S_1") (pintype "passive"))
      (node (ref "SV1") (pin "33") (pinfunction "33_33") (pintype "passive"))
    )
    (net (code "76") (name "V-") (class "Default")
      (node (ref "C48") (pin "1") (pinfunction "1_1") (pintype "passive"))
      (node (ref "C49") (pin "1") (pinfunction "1_1") (pintype "passive"))
      (node (ref "C50") (pin "1") (pinfunction "1_1") (pintype "passive"))
      (node (ref "C51") (pin "1") (pinfunction "1_1") (pintype "passive"))
      (node (ref "C52") (pin "1") (pinfunction "1_1") (pintype "passive"))
      (node (ref "C53") (pin "1") (pinfunction "1_1") (pintype "passive"))
      (node (ref "C54") (pin "1") (pinfunction "1_1") (pintype "passive"))
      (node (ref "C55") (pin "1") (pinfunction "1_1") (pintype "passive"))
      (node (ref "C56") (pin "1") (pinfunction "1_1") (pintype "passive"))
      (node (ref "C57") (pin "1") (pinfunction "1_1") (pintype "passive"))
      (node (ref "IC1") (pin "11") (pinfunction "V-_11") (pintype "power_in"))
      (node (ref "IC10") (pin "1") (pinfunction "V+_1") (pintype "power_in"))
      (node (ref "IC2") (pin "11") (pinfunction "V-_11") (pintype "power_in"))
      (node (ref "IC3") (pin "11") (pinfunction "V-_11") (pintype "power_in"))
      (node (ref "IC4") (pin "11") (pinfunction "V-_11") (pintype "power_in"))
      (node (ref "IC5") (pin "11") (pinfunction "V-_11") (pintype "power_in"))
      (node (ref "IC6") (pin "11") (pinfunction "V-_11") (pintype "power_in"))
      (node (ref "IC7") (pin "11") (pinfunction "V-_11") (pintype "power_in"))
      (node (ref "IC8") (pin "11") (pinfunction "V-_11") (pintype "power_in"))
      (node (ref "IC9") (pin "1") (pinfunction "V+_1") (pintype "power_in"))
      (node (ref "IO-AN") (pin "4") (pinfunction "4_4") (pintype "passive"))
      (node (ref "J1") (pin "3") (pinfunction "S_3") (pintype "passive"))
      (node (ref "SV1") (pin "35") (pinfunction "35_35") (pintype "passive"))
    )
    (net (code "77") (name "unconnected-(IC9-NC-Pad2)") (class "Default")
      (node (ref "IC9") (pin "2") (pinfunction "NC_2") (pintype "no_connect"))
    )
    (net (code "78") (name "unconnected-(IC9-NC-Pad3)") (class "Default")
      (node (ref "IC9") (pin "3") (pinfunction "NC_3") (pintype "no_connect"))
    )
    (net (code "79") (name "unconnected-(IC9-NC-Pad13)") (class "Default")
      (node (ref "IC9") (pin "13") (pinfunction "NC_13") (pintype "no_connect"))
    )
    (net (code "80") (name "unconnected-(IC10-NC-Pad2)") (class "Default")
      (node (ref "IC10") (pin "2") (pinfunction "NC_2") (pintype "no_connect"))
    )
    (net (code "81") (name "unconnected-(IC10-NC-Pad3)") (class "Default")
      (node (ref "IC10") (pin "3") (pinfunction "NC_3") (pintype "no_connect"))
    )
    (net (code "82") (name "unconnected-(IC10-NC-Pad13)") (class "Default")
      (node (ref "IC10") (pin "13") (pinfunction "NC_13") (pintype "no_connect"))
    )
    (net (code "83") (name "unconnected-(IO-AN-Pad3)") (class "Default")
      (node (ref "IO-AN") (pin "3") (pinfunction "3_3") (pintype "passive"))
    )
    (net (code "84") (name "unconnected-(SV1-Pad36)") (class "Default")
      (node (ref "SV1") (pin "36") (pinfunction "36_36") (pintype "passive"))
    )
  )
)
